# pogo.net
KiCad netlist of a schematic drawn in EAGLE
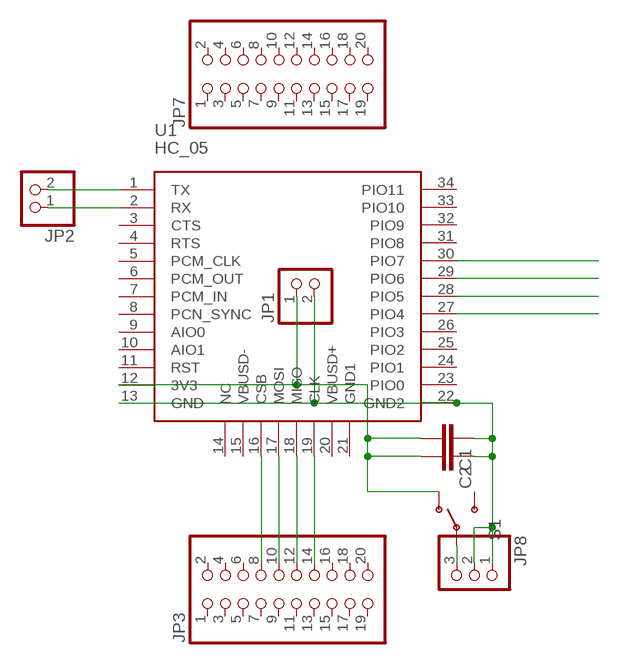
[diagram p0: schematic, sheet 1]

(export (version "E")
  (design (tool "Eeschema 10.0.6"))
  (components
    (comp (ref "C1")
      (value "C-EUC0805")
      (footprint "eagle-import:C0805")
      (libsource (lib "eagle-import") (part "C-EUC0805"))
    )
    (comp (ref "C2")
      (value "C-EUC0805")
      (footprint "eagle-import:C0805")
      (libsource (lib "eagle-import") (part "C-EUC0805"))
    )
    (comp (ref "JP1")
      (value "PINHD-1X2")
      (footprint "eagle-import:1X02")
      (libsource (lib "eagle-import") (part "PINHD-1X2"))
    )
    (comp (ref "JP2")
      (value "PINHD-1X2")
      (footprint "eagle-import:1X02")
      (libsource (lib "eagle-import") (part "PINHD-1X2"))
    )
    (comp (ref "JP3")
      (value "PINHD-2X10")
      (footprint "eagle-import:2X10")
      (libsource (lib "eagle-import") (part "PINHD-2X10"))
    )
    (comp (ref "JP7")
      (value "PINHD-2X10")
      (footprint "eagle-import:2X10")
      (libsource (lib "eagle-import") (part "PINHD-2X10"))
    )
    (comp (ref "JP8")
      (value "PINHD-1X3")
      (footprint "eagle-import:1X03")
      (libsource (lib "eagle-import") (part "PINHD-1X3"))
    )
    (comp (ref "S1")
      (value "SWITCH-SPDT-SMD-A")
      (footprint "eagle-import:SWITCH-SPST-SMD-A")
      (libsource (lib "eagle-import") (part "SWITCH-SPDT-SMD-A"))
    )
    (comp (ref "U1")
      (value "HC_05")
      (footprint "eagle-import:BLUETOOTH_SMD")
      (libsource (lib "eagle-import") (part "HC_05"))
    )
  )
  (nets
    (net (code "1") (name "Net-(S1-O)") (class "Default")
      (node (ref "C1") (pin "2") (pinfunction "2_2") (pintype "passive"))
      (node (ref "C2") (pin "2") (pinfunction "2_2") (pintype "passive"))
      (node (ref "JP1") (pin "1") (pinfunction "1_1") (pintype "passive"))
      (node (ref "S1") (pin "1") (pinfunction "O_1") (pintype "passive"))
      (node (ref "U1") (pin "12") (pinfunction "3V3_12") (pintype "bidirectional"))
    )
    (net (code "2") (name "Net-(S1-P)") (class "Default")
      (node (ref "JP8") (pin "3") (pinfunction "3_3") (pintype "passive"))
      (node (ref "S1") (pin "2") (pinfunction "P_2") (pintype "passive"))
    )
    (net (code "3") (name "Net-(U1-CLK)") (class "Default")
      (node (ref "JP3") (pin "14") (pinfunction "14_14") (pintype "passive"))
      (node (ref "U1") (pin "19") (pinfunction "CLK_19") (pintype "bidirectional"))
    )
    (net (code "4") (name "Net-(U1-CSB)") (class "Default")
      (node (ref "JP3") (pin "8") (pinfunction "8_8") (pintype "passive"))
      (node (ref "U1") (pin "16") (pinfunction "CSB_16") (pintype "bidirectional"))
    )
    (net (code "5") (name "Net-(U1-GND)") (class "Default")
      (node (ref "C1") (pin "1") (pinfunction "1_1") (pintype "passive"))
      (node (ref "C2") (pin "1") (pinfunction "1_1") (pintype "passive"))
      (node (ref "JP1") (pin "2") (pinfunction "2_2") (pintype "passive"))
      (node (ref "JP8") (pin "1") (pinfunction "1_1") (pintype "passive"))
      (node (ref "JP8") (pin "2") (pinfunction "2_2") (pintype "passive"))
      (node (ref "U1") (pin "13") (pinfunction "GND_13") (pintype "bidirectional"))
      (node (ref "U1") (pin "22") (pinfunction "GND2_22") (pintype "bidirectional"))
    )
    (net (code "6") (name "Net-(U1-MISO)") (class "Default")
      (node (ref "JP3") (pin "12") (pinfunction "12_12") (pintype "passive"))
      (node (ref "U1") (pin "18") (pinfunction "MISO_18") (pintype "bidirectional"))
    )
    (net (code "7") (name "Net-(U1-MOSI)") (class "Default")
      (node (ref "JP3") (pin "10") (pinfunction "10_10") (pintype "passive"))
      (node (ref "U1") (pin "17") (pinfunction "MOSI_17") (pintype "bidirectional"))
    )
    (net (code "8") (name "Net-(U1-RX)") (class "Default")
      (node (ref "JP2") (pin "1") (pinfunction "1_1") (pintype "passive"))
      (node (ref "U1") (pin "2") (pinfunction "RX_2") (pintype "bidirectional"))
    )
    (net (code "9") (name "Net-(U1-TX)") (class "Default")
      (node (ref "JP2") (pin "2") (pinfunction "2_2") (pintype "passive"))
      (node (ref "U1") (pin "1") (pinfunction "TX_1") (pintype "bidirectional"))
    )
    (net (code "10") (name "unconnected-(JP3-Pad1)") (class "Default")
      (node (ref "JP3") (pin "1") (pinfunction "1_1") (pintype "passive"))
    )
    (net (code "11") (name "unconnected-(JP3-Pad2)") (class "Default")
      (node (ref "JP3") (pin "2") (pinfunction "2_2") (pintype "passive"))
    )
    (net (code "12") (name "unconnected-(JP3-Pad3)") (class "Default")
      (node (ref "JP3") (pin "3") (pinfunction "3_3") (pintype "passive"))
    )
    (net (code "13") (name "unconnected-(JP3-Pad4)") (class "Default")
      (node (ref "JP3") (pin "4") (pinfunction "4_4") (pintype "passive"))
    )
    (net (code "14") (name "unconnected-(JP3-Pad5)") (class "Default")
      (node (ref "JP3") (pin "5") (pinfunction "5_5") (pintype "passive"))
    )
    (net (code "15") (name "unconnected-(JP3-Pad6)") (class "Default")
      (node (ref "JP3") (pin "6") (pinfunction "6_6") (pintype "passive"))
    )
    (net (code "16") (name "unconnected-(JP3-Pad7)") (class "Default")
      (node (ref "JP3") (pin "7") (pinfunction "7_7") (pintype "passive"))
    )
    (net (code "17") (name "unconnected-(JP3-Pad9)") (class "Default")
      (node (ref "JP3") (pin "9") (pinfunction "9_9") (pintype "passive"))
    )
    (net (code "18") (name "unconnected-(JP3-Pad11)") (class "Default")
      (node (ref "JP3") (pin "11") (pinfunction "11_11") (pintype "passive"))
    )
    (net (code "19") (name "unconnected-(JP3-Pad13)") (class "Default")
      (node (ref "JP3") (pin "13") (pinfunction "13_13") (pintype "passive"))
    )
    (net (code "20") (name "unconnected-(JP3-Pad15)") (class "Default")
      (node (ref "JP3") (pin "15") (pinfunction "15_15") (pintype "passive"))
    )
    (net (code "21") (name "unconnected-(JP3-Pad16)") (class "Default")
      (node (ref "JP3") (pin "16") (pinfunction "16_16") (pintype "passive"))
    )
    (net (code "22") (name "unconnected-(JP3-Pad17)") (class "Default")
      (node (ref "JP3") (pin "17") (pinfunction "17_17") (pintype "passive"))
    )
    (net (code "23") (name "unconnected-(JP3-Pad18)") (class "Default")
      (node (ref "JP3") (pin "18") (pinfunction "18_18") (pintype "passive"))
    )
    (net (code "24") (name "unconnected-(JP3-Pad19)") (class "Default")
      (node (ref "JP3") (pin "19") (pinfunction "19_19") (pintype "passive"))
    )
    (net (code "25") (name "unconnected-(JP3-Pad20)") (class "Default")
      (node (ref "JP3") (pin "20") (pinfunction "20_20") (pintype "passive"))
    )
    (net (code "26") (name "unconnected-(JP7-Pad1)") (class "Default")
      (node (ref "JP7") (pin "1") (pinfunction "1_1") (pintype "passive"))
    )
    (net (code "27") (name "unconnected-(JP7-Pad2)") (class "Default")
      (node (ref "JP7") (pin "2") (pinfunction "2_2") (pintype "passive"))
    )
    (net (code "28") (name "unconnected-(JP7-Pad3)") (class "Default")
      (node (ref "JP7") (pin "3") (pinfunction "3_3") (pintype "passive"))
    )
    (net (code "29") (name "unconnected-(JP7-Pad4)") (class "Default")
      (node (ref "JP7") (pin "4") (pinfunction "4_4") (pintype "passive"))
    )
    (net (code "30") (name "unconnected-(JP7-Pad5)") (class "Default")
      (node (ref "JP7") (pin "5") (pinfunction "5_5") (pintype "passive"))
    )
    (net (code "31") (name "unconnected-(JP7-Pad6)") (class "Default")
      (node (ref "JP7") (pin "6") (pinfunction "6_6") (pintype "passive"))
    )
    (net (code "32") (name "unconnected-(JP7-Pad7)") (class "Default")
      (node (ref "JP7") (pin "7") (pinfunction "7_7") (pintype "passive"))
    )
    (net (code "33") (name "unconnected-(JP7-Pad8)") (class "Default")
      (node (ref "JP7") (pin "8") (pinfunction "8_8") (pintype "passive"))
    )
    (net (code "34") (name "unconnected-(JP7-Pad9)") (class "Default")
      (node (ref "JP7") (pin "9") (pinfunction "9_9") (pintype "passive"))
    )
    (net (code "35") (name "unconnected-(JP7-Pad10)") (class "Default")
      (node (ref "JP7") (pin "10") (pinfunction "10_10") (pintype "passive"))
    )
    (net (code "36") (name "unconnected-(JP7-Pad11)") (class "Default")
      (node (ref "JP7") (pin "11") (pinfunction "11_11") (pintype "passive"))
    )
    (net (code "37") (name "unconnected-(JP7-Pad12)") (class "Default")
      (node (ref "JP7") (pin "12") (pinfunction "12_12") (pintype "passive"))
    )
    (net (code "38") (name "unconnected-(JP7-Pad13)") (class "Default")
      (node (ref "JP7") (pin "13") (pinfunction "13_13") (pintype "passive"))
    )
    (net (code "39") (name "unconnected-(JP7-Pad14)") (class "Default")
      (node (ref "JP7") (pin "14") (pinfunction "14_14") (pintype "passive"))
    )
    (net (code "40") (name "unconnected-(JP7-Pad15)") (class "Default")
      (node (ref "JP7") (pin "15") (pinfunction "15_15") (pintype "passive"))
    )
    (net (code "41") (name "unconnected-(JP7-Pad16)") (class "Default")
      (node (ref "JP7") (pin "16") (pinfunction "16_16") (pintype "passive"))
    )
    (net (code "42") (name "unconnected-(JP7-Pad17)") (class "Default")
      (node (ref "JP7") (pin "17") (pinfunction "17_17") (pintype "passive"))
    )
    (net (code "43") (name "unconnected-(JP7-Pad18)") (class "Default")
      (node (ref "JP7") (pin "18") (pinfunction "18_18") (pintype "passive"))
    )
    (net (code "44") (name "unconnected-(JP7-Pad19)") (class "Default")
      (node (ref "JP7") (pin "19") (pinfunction "19_19") (pintype "passive"))
    )
    (net (code "45") (name "unconnected-(JP7-Pad20)") (class "Default")
      (node (ref "JP7") (pin "20") (pinfunction "20_20") (pintype "passive"))
    )
    (net (code "46") (name "unconnected-(S1-S-Pad3)") (class "Default")
      (node (ref "S1") (pin "3") (pinfunction "S_3") (pintype "passive"))
    )
    (net (code "47") (name "unconnected-(U1-AIO0-Pad9)") (class "Default")
      (node (ref "U1") (pin "9") (pinfunction "AIO0_9") (pintype "bidirectional"))
    )
    (net (code "48") (name "unconnected-(U1-AIO1-Pad10)") (class "Default")
      (node (ref "U1") (pin "10") (pinfunction "AIO1_10") (pintype "bidirectional"))
    )
    (net (code "49") (name "unconnected-(U1-CTS-Pad3)") (class "Default")
      (node (ref "U1") (pin "3") (pinfunction "CTS_3") (pintype "bidirectional"))
    )
    (net (code "50") (name "unconnected-(U1-GND1-Pad21)") (class "Default")
      (node (ref "U1") (pin "21") (pinfunction "GND1_21") (pintype "bidirectional"))
    )
    (net (code "51") (name "unconnected-(U1-NC-Pad14)") (class "Default")
      (node (ref "U1") (pin "14") (pinfunction "NC_14") (pintype "bidirectional"))
    )
    (net (code "52") (name "unconnected-(U1-PCM_CLK-Pad5)") (class "Default")
      (node (ref "U1") (pin "5") (pinfunction "PCM_CLK_5") (pintype "bidirectional"))
    )
    (net (code "53") (name "unconnected-(U1-PCM_IN-Pad7)") (class "Default")
      (node (ref "U1") (pin "7") (pinfunction "PCM_IN_7") (pintype "bidirectional"))
    )
    (net (code "54") (name "unconnected-(U1-PCM_OUT-Pad6)") (class "Default")
      (node (ref "U1") (pin "6") (pinfunction "PCM_OUT_6") (pintype "bidirectional"))
    )
    (net (code "55") (name "unconnected-(U1-PCN_SYNC-Pad8)") (class "Default")
      (node (ref "U1") (pin "8") (pinfunction "PCN_SYNC_8") (pintype "bidirectional"))
    )
    (net (code "56") (name "unconnected-(U1-PIO0-Pad23)") (class "Default")
      (node (ref "U1") (pin "23") (pinfunction "PIO0_23") (pintype "bidirectional"))
    )
    (net (code "57") (name "unconnected-(U1-PIO1-Pad24)") (class "Default")
      (node (ref "U1") (pin "24") (pinfunction "PIO1_24") (pintype "bidirectional"))
    )
    (net (code "58") (name "unconnected-(U1-PIO2-Pad25)") (class "Default")
      (node (ref "U1") (pin "25") (pinfunction "PIO2_25") (pintype "bidirectional"))
    )
    (net (code "59") (name "unconnected-(U1-PIO3-Pad26)") (class "Default")
      (node (ref "U1") (pin "26") (pinfunction "PIO3_26") (pintype "bidirectional"))
    )
    (net (code "60") (name "unconnected-(U1-PIO4-Pad27)") (class "Default")
      (node (ref "U1") (pin "27") (pinfunction "PIO4_27") (pintype "bidirectional"))
    )
    (net (code "61") (name "unconnected-(U1-PIO5-Pad28)") (class "Default")
      (node (ref "U1") (pin "28") (pinfunction "PIO5_28") (pintype "bidirectional"))
    )
    (net (code "62") (name "unconnected-(U1-PIO6-Pad29)") (class "Default")
      (node (ref "U1") (pin "29") (pinfunction "PIO6_29") (pintype "bidirectional"))
    )
    (net (code "63") (name "unconnected-(U1-PIO7-Pad30)") (class "Default")
      (node (ref "U1") (pin "30") (pinfunction "PIO7_30") (pintype "bidirectional"))
    )
    (net (code "64") (name "unconnected-(U1-PIO8-Pad31)") (class "Default")
      (node (ref "U1") (pin "31") (pinfunction "PIO8_31") (pintype "bidirectional"))
    )
    (net (code "65") (name "unconnected-(U1-PIO9-Pad32)") (class "Default")
      (node (ref "U1") (pin "32") (pinfunction "PIO9_32") (pintype "bidirectional"))
    )
    (net (code "66") (name "unconnected-(U1-PIO10-Pad33)") (class "Default")
      (node (ref "U1") (pin "33") (pinfunction "PIO10_33") (pintype "bidirectional"))
    )
    (net (code "67") (name "unconnected-(U1-PIO11-Pad34)") (class "Default")
      (node (ref "U1") (pin "34") (pinfunction "PIO11_34") (pintype "bidirectional"))
    )
    (net (code "68") (name "unconnected-(U1-RST-Pad11)") (class "Default")
      (node (ref "U1") (pin "11") (pinfunction "RST_11") (pintype "bidirectional"))
    )
    (net (code "69") (name "unconnected-(U1-RTS-Pad4)") (class "Default")
      (node (ref "U1") (pin "4") (pinfunction "RTS_4") (pintype "bidirectional"))
    )
    (net (code "70") (name "unconnected-(U1-VBUSD+-Pad20)") (class "Default")
      (node (ref "U1") (pin "20") (pinfunction "VBUSD+_20") (pintype "bidirectional"))
    )
    (net (code "71") (name "unconnected-(U1-VBUSD--Pad15)") (class "Default")
      (node (ref "U1") (pin "15") (pinfunction "VBUSD-_15") (pintype "bidirectional"))
    )
  )
)
